# Power.net
KiCad netlist of a schematic drawn in Altium Designer
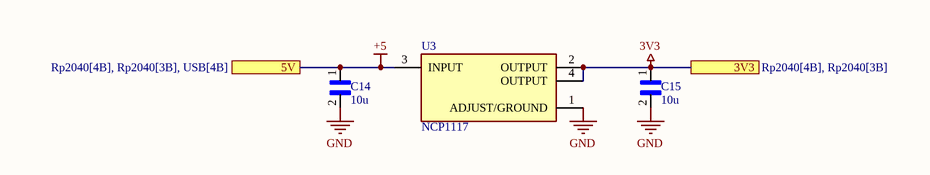
[diagram p0: Power.SchDoc]

(export (version "E")
  (design (tool "Eeschema 10.0.6"))
  (components
    (comp (ref "C14")
      (value "10u")
      (footprint "SMD Capacator")
      (libsource (lib "Basic") (part "SMD Capacator"))
    )
    (comp (ref "C15")
      (value "10u")
      (footprint "SMD Capacator")
      (libsource (lib "Basic") (part "SMD Capacator"))
    )
    (comp (ref "U3") (value "NCP1117") (footprint "NCP1117") (libsource (lib "Basic") (part "NCP1117")))
  )
  (nets
    (net (code "1") (name "+5") (class "Default")
      (node (ref "C14") (pin "1") (pinfunction "1_1") (pintype "passive"))
      (node (ref "U3") (pin "3") (pinfunction "INPUT_3") (pintype "power_in"))
    )
    (net (code "2") (name "3V3") (class "Default")
      (node (ref "C15") (pin "1") (pinfunction "1_1") (pintype "passive"))
      (node (ref "U3") (pin "2") (pinfunction "OUTPUT_2") (pintype "power_in"))
      (node (ref "U3") (pin "4") (pinfunction "OUTPUT_4") (pintype "power_in"))
    )
    (net (code "3") (name "GND") (class "Default")
      (node (ref "C14") (pin "2") (pinfunction "2_2") (pintype "passive"))
      (node (ref "C15") (pin "2") (pinfunction "2_2") (pintype "passive"))
      (node (ref "U3") (pin "1") (pinfunction "ADJUST/GROUND_1") (pintype "passive"))
    )
  )
)
